# usb_adapter.net
KiCad netlist of a schematic drawn in EAGLE
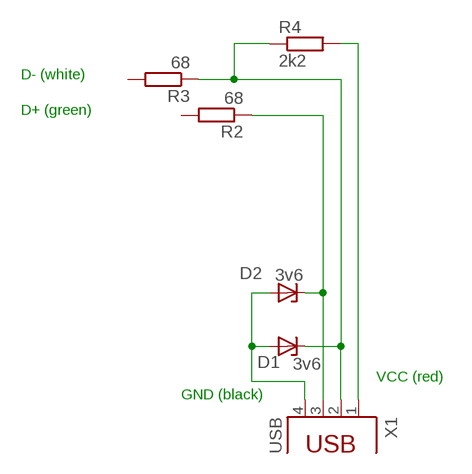
[diagram p0: schematic, sheet 1]

(export (version "E")
  (design (tool "Eeschema 10.0.6"))
  (components
    (comp (ref "D1")
      (value "3v6")
      (footprint "eagle-import:DO34Z7")
      (libsource (lib "eagle-import") (part "ZENER-DIODEDO34-7"))
    )
    (comp (ref "D2")
      (value "3v6")
      (footprint "eagle-import:DO34Z7")
      (libsource (lib "eagle-import") (part "ZENER-DIODEDO34-7"))
    )
    (comp (ref "R2")
      (value "68")
      (footprint "eagle-import:0204_7")
      (libsource (lib "eagle-import") (part "R-EU_0204/7"))
    )
    (comp (ref "R3")
      (value "68")
      (footprint "eagle-import:0204_7")
      (libsource (lib "eagle-import") (part "R-EU_0204/7"))
    )
    (comp (ref "R4")
      (value "2k2")
      (footprint "eagle-import:0204_7")
      (libsource (lib "eagle-import") (part "R-EU_0204/7"))
    )
    (comp (ref "X1")
      (value "USB")
      (footprint "eagle-import:PN61729")
      (libsource (lib "eagle-import") (part "PN61729"))
    )
  )
  (nets
    (net (code "1") (name "Net-(D1-PadA)") (class "Default")
      (node (ref "D1") (pin "A") (pinfunction "A_A") (pintype "passive"))
      (node (ref "D2") (pin "A") (pinfunction "A_A") (pintype "passive"))
      (node (ref "X1") (pin "4") (pinfunction "4_4") (pintype "passive"))
    )
    (net (code "2") (name "Net-(D1-PadC)") (class "Default")
      (node (ref "D1") (pin "C") (pinfunction "C_C") (pintype "passive"))
      (node (ref "R3") (pin "1") (pinfunction "1_1") (pintype "passive"))
      (node (ref "R4") (pin "1") (pinfunction "1_1") (pintype "passive"))
      (node (ref "X1") (pin "2") (pinfunction "2_2") (pintype "passive"))
    )
    (net (code "3") (name "Net-(D2-PadC)") (class "Default")
      (node (ref "D2") (pin "C") (pinfunction "C_C") (pintype "passive"))
      (node (ref "R2") (pin "1") (pinfunction "1_1") (pintype "passive"))
      (node (ref "X1") (pin "3") (pinfunction "3_3") (pintype "passive"))
    )
    (net (code "4") (name "Net-(R4-Pad2)") (class "Default")
      (node (ref "R4") (pin "2") (pinfunction "2_2") (pintype "passive"))
      (node (ref "X1") (pin "1") (pinfunction "1_1") (pintype "passive"))
    )
    (net (code "5") (name "unconnected-(R2-Pad2)") (class "Default")
      (node (ref "R2") (pin "2") (pinfunction "2_2") (pintype "passive"))
    )
    (net (code "6") (name "unconnected-(R3-Pad2)") (class "Default")
      (node (ref "R3") (pin "2") (pinfunction "2_2") (pintype "passive"))
    )
  )
)
